# WGA_IR.net
KiCad netlist of a schematic drawn in Altium Designer
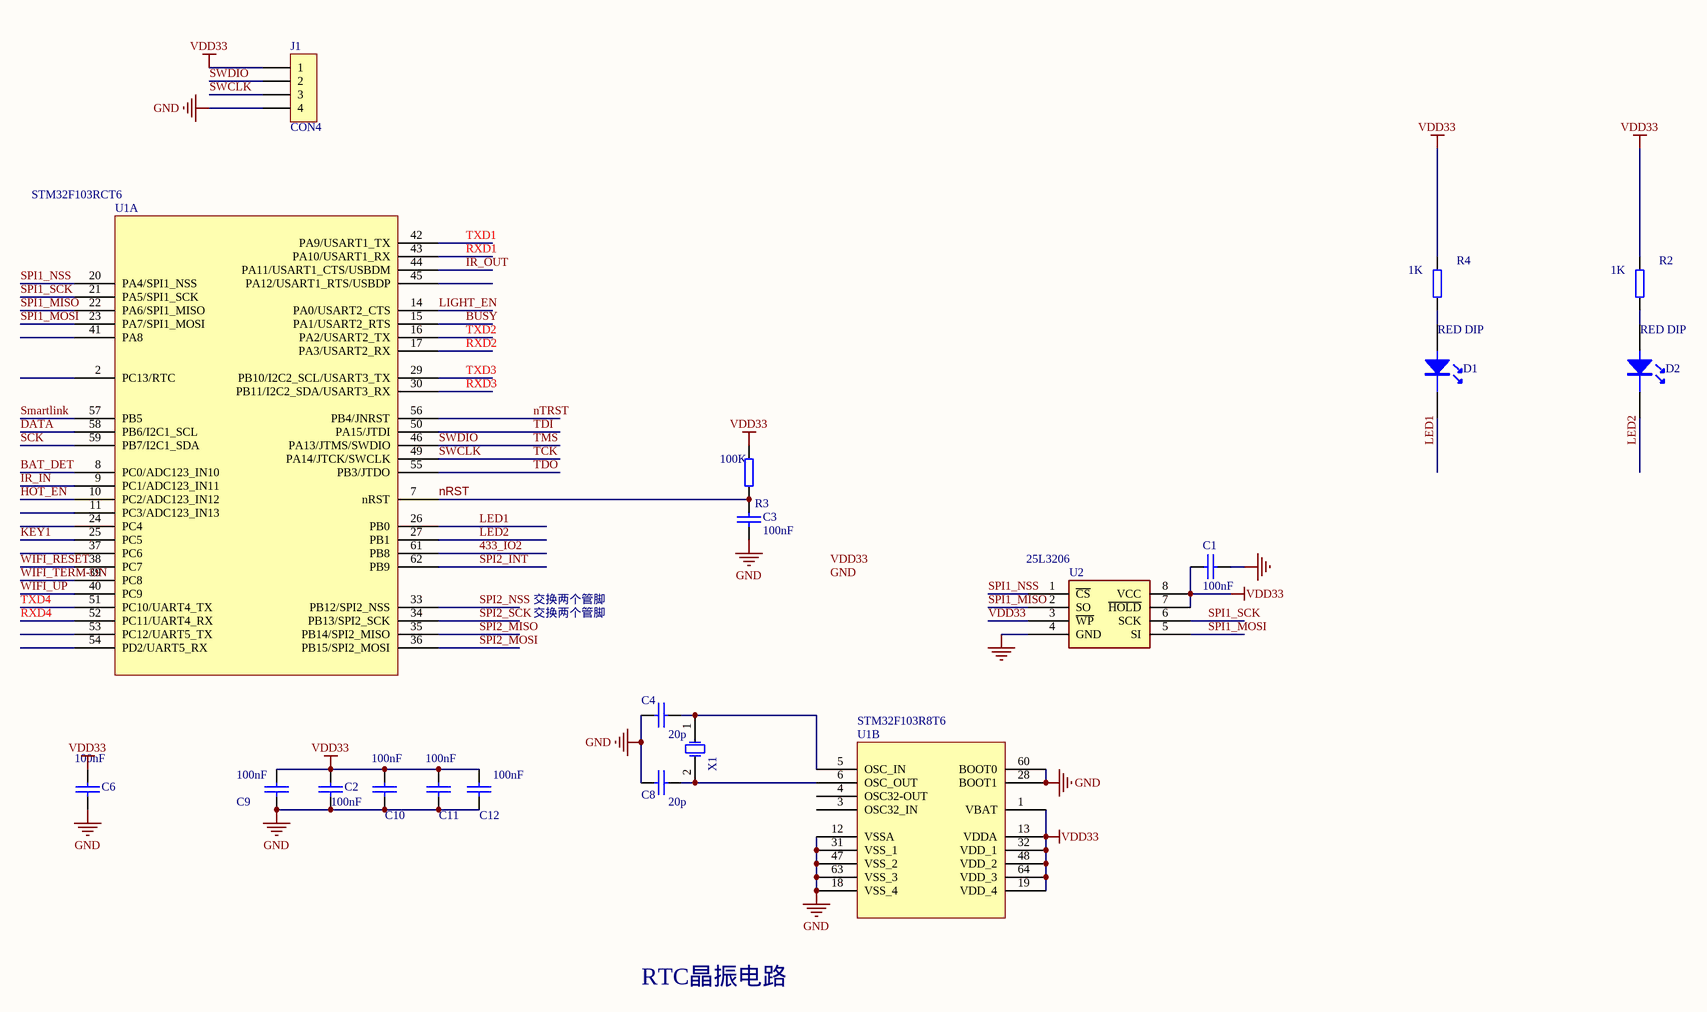
[diagram p0: WGA_IR.SchDoc]

(export (version "E")
  (design (tool "Eeschema 10.0.6"))
  (components
    (comp (ref "C1")
      (value "100nF")
      (footprint "C0603")
      (description "CAP CER 0.1UF 50V Y5V 0603")
      (fields
        (field (name "MANUFACTURER") "Yageo")
        (field (name "MANUFACTURER PART NUMBER") "CC0603ZRY5V9BB104")
      )
      (libsource (lib "") (part "C0603_100nF_1"))
    )
    (comp (ref "C2")
      (value "100nF")
      (footprint "C0603")
      (description "CAP CER 0.1UF 50V Y5V 0603")
      (fields
        (field (name "MANUFACTURER") "Yageo")
        (field (name "MANUFACTURER PART NUMBER") "CC0603ZRY5V9BB104")
      )
      (libsource (lib "") (part "C0603_100nF_1"))
    )
    (comp (ref "C3")
      (value "100nF")
      (footprint "C0603")
      (description "CAP CER 0.1UF 50V Y5V 0603")
      (fields
        (field (name "MANUFACTURER") "Yageo")
        (field (name "MANUFACTURER PART NUMBER") "CC0603ZRY5V9BB104")
      )
      (libsource (lib "电容") (part "C0603_100nF"))
    )
    (comp (ref "C4")
      (value "20p")
      (footprint "C0603")
      (description "CAP CER 20PF 50V 5% NPO 0603")
      (fields
        (field (name "MANUFACTURER") "Yageo")
        (field (name "MANUFACTURER PART NUMBER") "CC0603JRNPO9BN200")
      )
      (libsource (lib "红外微波探测") (part "C0603_20p"))
    )
    (comp (ref "C6")
      (value "100nF")
      (footprint "C0603")
      (description "CAP CER 0.1UF 50V Y5V 0603")
      (fields
        (field (name "MANUFACTURER") "Yageo")
        (field (name "MANUFACTURER PART NUMBER") "CC0603ZRY5V9BB104")
      )
      (libsource (lib "") (part "C0603_100nF_1"))
    )
    (comp (ref "C8")
      (value "20p")
      (footprint "C0603")
      (description "CAP CER 20PF 50V 5% NPO 0603")
      (fields
        (field (name "MANUFACTURER") "Yageo")
        (field (name "MANUFACTURER PART NUMBER") "CC0603JRNPO9BN200")
      )
      (libsource (lib "红外微波探测") (part "C0603_20p"))
    )
    (comp (ref "C9")
      (value "100nF")
      (footprint "C0603")
      (description "CAP CER 0.1UF 50V Y5V 0603")
      (fields
        (field (name "MANUFACTURER") "Yageo")
        (field (name "MANUFACTURER PART NUMBER") "CC0603ZRY5V9BB104")
      )
      (libsource (lib "") (part "C0603_100nF_1"))
    )
    (comp (ref "C10")
      (value "100nF")
      (footprint "C0603")
      (description "CAP CER 0.1UF 50V Y5V 0603")
      (fields
        (field (name "MANUFACTURER") "Yageo")
        (field (name "MANUFACTURER PART NUMBER") "CC0603ZRY5V9BB104")
      )
      (libsource (lib "") (part "C0603_100nF_1"))
    )
    (comp (ref "C11")
      (value "100nF")
      (footprint "C0603")
      (description "CAP CER 0.1UF 50V Y5V 0603")
      (fields
        (field (name "MANUFACTURER") "Yageo")
        (field (name "MANUFACTURER PART NUMBER") "CC0603ZRY5V9BB104")
      )
      (libsource (lib "") (part "C0603_100nF_1"))
    )
    (comp (ref "C12")
      (value "100nF")
      (footprint "C0603")
      (description "CAP CER 0.1UF 50V Y5V 0603")
      (fields
        (field (name "MANUFACTURER") "Yageo")
        (field (name "MANUFACTURER PART NUMBER") "CC0603ZRY5V9BB104")
      )
      (libsource (lib "") (part "C0603_100nF_1"))
    )
    (comp (ref "D1")
      (value "RED DIP")
      (footprint "T1-3MM_N")
      (description "LED SUPER RED 0603 SMD VF=2V  I=20mA")
      (fields
        (field (name "MANUFACTURER") "Vishay Semiconductor Opto Division")
        (field (name "MANUFACTURER PART NUMBER") "VLMS1300-GS08")
      )
      (libsource (lib "二极管") (part "LED-D0603"))
    )
    (comp (ref "D2")
      (value "RED DIP")
      (footprint "T1-3MM_N")
      (description "LED SUPER RED 0603 SMD VF=2V  I=20mA")
      (fields
        (field (name "MANUFACTURER") "Vishay Semiconductor Opto Division")
        (field (name "MANUFACTURER PART NUMBER") "VLMS1300-GS08")
      )
      (libsource (lib "二极管") (part "LED-D0603"))
    )
    (comp (ref "J1")
      (value "CON4")
      (footprint "SIP4")
      (description "2.54mm dip")
      (libsource (lib "接插件") (part "CON4"))
    )
    (comp (ref "R2")
      (value "1K")
      (footprint "R0603")
      (description "RES 1.0K OHM 1/10W 5% 0603 SMD")
      (fields
        (field (name "MANUFACTURER") "Yageo")
        (field (name "MANUFACTURER PART NUMBER") "RC0603JR-071KL")
      )
      (libsource (lib "电阻") (part "R0603_1K_5%"))
    )
    (comp (ref "R3")
      (value "100K")
      (footprint "R0603")
      (description "RES 100K OHM 1/10W 5% 0603 SMD")
      (fields
        (field (name "MANUFACTURER") "Yageo")
        (field (name "MANUFACTURER PART NUMBER") "RC0603JR-07100KL")
      )
      (libsource (lib "电阻") (part "R0603_100K_5%"))
    )
    (comp (ref "R4")
      (value "1K")
      (footprint "R0603")
      (description "RES 1.0K OHM 1/10W 5% 0603 SMD")
      (fields
        (field (name "MANUFACTURER") "Yageo")
        (field (name "MANUFACTURER PART NUMBER") "RC0603JR-071KL")
      )
      (libsource (lib "电阻") (part "R0603_1K_5%"))
    )
    (comp (ref "U1")
      (value "STM32F103RCT6")
      (footprint "LQFP64")
      (description "MCU ARM 128KB FLASH MEM 64-LQFP")
      (fields (field (name "MANUFACTURER") "STMicroelectronics"))
      (libsource (lib "集成电路") (part "STM32F103RC"))
    )
    (comp (ref "U2")
      (value "25L3206")
      (footprint "SSOP8")
      (description "IC FLASH 32MBIT 86MHZ 8SOP 32M (4M x 8)")
      (fields
        (field (name "MANUFACTURER") "Macronix")
        (field (name "MANUFACTURER PART NUMBER") "MX25L3206EM2I-12G")
      )
      (libsource (lib "红外微波探测") (part "25L3206"))
    )
    (comp (ref "X1")
      (value "9C-8.000MBBK-T")
      (footprint "XTAL2")
      (description "CRYSTAL 8.000MHZ 20PF SMD")
      (fields (field (name "MANUFACTURER") "TXC CORPORATION"))
      (libsource (lib "红外微波探测") (part "CRYSTAL-XTAL2"))
    )
  )
  (nets
    (net (code "1") (name "/433_IO2") (class "Default")
      (node (ref "U1") (pin "61") (pinfunction "PB8_61") (pintype "passive"))
    )
    (net (code "2") (name "/BAT_DET") (class "Default")
      (node (ref "U1") (pin "8") (pinfunction "PC0/ADC123_IN10_8") (pintype "passive"))
    )
    (net (code "3") (name "/BUSY") (class "Default")
      (node (ref "U1") (pin "15") (pinfunction "PA1/USART2_RTS_15") (pintype "passive"))
    )
    (net (code "4") (name "/DATA") (class "Default")
      (node (ref "U1") (pin "58") (pinfunction "PB6/I2C1_SCL_58") (pintype "passive"))
    )
    (net (code "5") (name "/HOT_EN") (class "Default")
      (node (ref "U1") (pin "10") (pinfunction "PC2/ADC123_IN12_10") (pintype "passive"))
    )
    (net (code "6") (name "/IR_IN") (class "Default")
      (node (ref "U1") (pin "9") (pinfunction "PC1/ADC123_IN11_9") (pintype "passive"))
    )
    (net (code "7") (name "/IR_OUT") (class "Default")
      (node (ref "U1") (pin "44") (pinfunction "PA11/USART1_CTS/USBDM_44") (pintype "passive"))
    )
    (net (code "8") (name "/KEY1") (class "Default")
      (node (ref "U1") (pin "25") (pinfunction "PC5_25") (pintype "passive"))
    )
    (net (code "9") (name "/LED1") (class "Default")
      (node (ref "D1") (pin "2") (pinfunction "2_2") (pintype "passive"))
      (node (ref "U1") (pin "26") (pinfunction "PB0_26") (pintype "passive"))
    )
    (net (code "10") (name "/LED2") (class "Default")
      (node (ref "D2") (pin "2") (pinfunction "2_2") (pintype "passive"))
      (node (ref "U1") (pin "27") (pinfunction "PB1_27") (pintype "passive"))
    )
    (net (code "11") (name "/LIGHT_EN") (class "Default")
      (node (ref "U1") (pin "14") (pinfunction "PA0/USART2_CTS_14") (pintype "passive"))
    )
    (net (code "12") (name "/RXD1") (class "Default")
      (node (ref "U1") (pin "43") (pinfunction "PA10/USART1_RX_43") (pintype "passive"))
    )
    (net (code "13") (name "/RXD2") (class "Default")
      (node (ref "U1") (pin "17") (pinfunction "PA3/USART2_RX_17") (pintype "passive"))
    )
    (net (code "14") (name "/RXD3") (class "Default")
      (node (ref "U1") (pin "30") (pinfunction "PB11/I2C2_SDA/USART3_RX_30") (pintype "passive"))
    )
    (net (code "15") (name "/RXD4") (class "Default")
      (node (ref "U1") (pin "52") (pinfunction "PC11/UART4_RX_52") (pintype "passive"))
    )
    (net (code "16") (name "/SCK") (class "Default")
      (node (ref "U1") (pin "59") (pinfunction "PB7/I2C1_SDA_59") (pintype "passive"))
    )
    (net (code "17") (name "/SPI1_MISO") (class "Default")
      (node (ref "U1") (pin "22") (pinfunction "PA6/SPI1_MISO_22") (pintype "passive"))
      (node (ref "U2") (pin "2") (pinfunction "SO_2") (pintype "passive"))
    )
    (net (code "18") (name "/SPI1_MOSI") (class "Default")
      (node (ref "U1") (pin "23") (pinfunction "PA7/SPI1_MOSI_23") (pintype "passive"))
      (node (ref "U2") (pin "5") (pinfunction "SI_5") (pintype "passive"))
    )
    (net (code "19") (name "/SPI1_NSS") (class "Default")
      (node (ref "U1") (pin "20") (pinfunction "PA4/SPI1_NSS_20") (pintype "passive"))
      (node (ref "U2") (pin "1") (pinfunction "~{CS}_1") (pintype "passive"))
    )
    (net (code "20") (name "/SPI1_SCK") (class "Default")
      (node (ref "U1") (pin "21") (pinfunction "PA5/SPI1_SCK_21") (pintype "passive"))
      (node (ref "U2") (pin "6") (pinfunction "SCK_6") (pintype "passive"))
    )
    (net (code "21") (name "/SPI2_INT") (class "Default")
      (node (ref "U1") (pin "62") (pinfunction "PB9_62") (pintype "passive"))
    )
    (net (code "22") (name "/SPI2_MISO") (class "Default")
      (node (ref "U1") (pin "35") (pinfunction "PB14/SPI2_MISO_35") (pintype "passive"))
    )
    (net (code "23") (name "/SPI2_MOSI") (class "Default")
      (node (ref "U1") (pin "36") (pinfunction "PB15/SPI2_MOSI_36") (pintype "passive"))
    )
    (net (code "24") (name "/SPI2_NSS") (class "Default")
      (node (ref "U1") (pin "33") (pinfunction "PB12/SPI2_NSS_33") (pintype "passive"))
    )
    (net (code "25") (name "/SPI2_SCK") (class "Default")
      (node (ref "U1") (pin "34") (pinfunction "PB13/SPI2_SCK_34") (pintype "passive"))
    )
    (net (code "26") (name "/SWCLK") (class "Default")
      (node (ref "J1") (pin "3") (pinfunction "3_3") (pintype "passive"))
      (node (ref "U1") (pin "49") (pinfunction "PA14/JTCK/SWCLK_49") (pintype "passive"))
    )
    (net (code "27") (name "/SWDIO") (class "Default")
      (node (ref "J1") (pin "2") (pinfunction "2_2") (pintype "passive"))
      (node (ref "U1") (pin "46") (pinfunction "PA13/JTMS/SWDIO_46") (pintype "passive"))
    )
    (net (code "28") (name "/Smartlink") (class "Default")
      (node (ref "U1") (pin "57") (pinfunction "PB5_57") (pintype "passive"))
    )
    (net (code "29") (name "/TDI") (class "Default")
      (node (ref "U1") (pin "50") (pinfunction "PA15/JTDI_50") (pintype "passive"))
    )
    (net (code "30") (name "/TDO") (class "Default")
      (node (ref "U1") (pin "55") (pinfunction "PB3/JTDO_55") (pintype "passive"))
    )
    (net (code "31") (name "/TXD1") (class "Default")
      (node (ref "U1") (pin "42") (pinfunction "PA9/USART1_TX_42") (pintype "passive"))
    )
    (net (code "32") (name "/TXD2") (class "Default")
      (node (ref "U1") (pin "16") (pinfunction "PA2/USART2_TX_16") (pintype "passive"))
    )
    (net (code "33") (name "/TXD3") (class "Default")
      (node (ref "U1") (pin "29") (pinfunction "PB10/I2C2_SCL/USART3_TX_29") (pintype "passive"))
    )
    (net (code "34") (name "/TXD4") (class "Default")
      (node (ref "U1") (pin "51") (pinfunction "PC10/UART4_TX_51") (pintype "passive"))
    )
    (net (code "35") (name "/WIFI_RESET") (class "Default")
      (node (ref "U1") (pin "38") (pinfunction "PC7_38") (pintype "passive"))
    )
    (net (code "36") (name "/WIFI_TERM-ON") (class "Default")
      (node (ref "U1") (pin "39") (pinfunction "PC8_39") (pintype "passive"))
    )
    (net (code "37") (name "/WIFI_UP") (class "Default")
      (node (ref "U1") (pin "40") (pinfunction "PC9_40") (pintype "passive"))
    )
    (net (code "38") (name "/nRST") (class "Default")
      (node (ref "C3") (pin "2") (pinfunction "2_2") (pintype "passive"))
      (node (ref "R3") (pin "1") (pinfunction "1_1") (pintype "passive"))
      (node (ref "U1") (pin "7") (pinfunction "nRST_7") (pintype "passive"))
    )
    (net (code "39") (name "/nTRST") (class "Default")
      (node (ref "U1") (pin "56") (pinfunction "PB4/JNRST_56") (pintype "passive"))
    )
    (net (code "40") (name "GND") (class "Default")
      (node (ref "C1") (pin "2") (pinfunction "2_2") (pintype "passive"))
      (node (ref "C10") (pin "2") (pinfunction "2_2") (pintype "passive"))
      (node (ref "C11") (pin "2") (pinfunction "2_2") (pintype "passive"))
      (node (ref "C12") (pin "2") (pinfunction "2_2") (pintype "passive"))
      (node (ref "C2") (pin "2") (pinfunction "2_2") (pintype "passive"))
      (node (ref "C3") (pin "1") (pinfunction "1_1") (pintype "passive"))
      (node (ref "C4") (pin "1") (pinfunction "1_1") (pintype "passive"))
      (node (ref "C6") (pin "2") (pinfunction "2_2") (pintype "passive"))
      (node (ref "C8") (pin "1") (pinfunction "1_1") (pintype "passive"))
      (node (ref "C9") (pin "2") (pinfunction "2_2") (pintype "passive"))
      (node (ref "J1") (pin "4") (pinfunction "4_4") (pintype "passive"))
      (node (ref "U1") (pin "12") (pinfunction "VSSA_12") (pintype "passive"))
      (node (ref "U1") (pin "18") (pinfunction "VSS_4_18") (pintype "passive"))
      (node (ref "U1") (pin "28") (pinfunction "BOOT1_28") (pintype "passive"))
      (node (ref "U1") (pin "31") (pinfunction "VSS_1_31") (pintype "passive"))
      (node (ref "U1") (pin "47") (pinfunction "VSS_2_47") (pintype "passive"))
      (node (ref "U1") (pin "60") (pinfunction "BOOT0_60") (pintype "passive"))
      (node (ref "U1") (pin "63") (pinfunction "VSS_3_63") (pintype "passive"))
      (node (ref "U2") (pin "4") (pinfunction "GND_4") (pintype "passive"))
    )
    (net (code "41") (name "Net-(D1-Pad1)") (class "Default")
      (node (ref "D1") (pin "1") (pinfunction "1_1") (pintype "passive"))
      (node (ref "R4") (pin "1") (pinfunction "1_1") (pintype "passive"))
    )
    (net (code "42") (name "Net-(D2-Pad1)") (class "Default")
      (node (ref "D2") (pin "1") (pinfunction "1_1") (pintype "passive"))
      (node (ref "R2") (pin "1") (pinfunction "1_1") (pintype "passive"))
    )
    (net (code "43") (name "Net-(U1B-OSC_IN)") (class "Default")
      (node (ref "C4") (pin "2") (pinfunction "2_2") (pintype "passive"))
      (node (ref "U1") (pin "5") (pinfunction "OSC_IN_5") (pintype "passive"))
      (node (ref "X1") (pin "1") (pinfunction "OSC1_1") (pintype "passive"))
    )
    (net (code "44") (name "Net-(U1B-OSC_OUT)") (class "Default")
      (node (ref "C8") (pin "2") (pinfunction "2_2") (pintype "passive"))
      (node (ref "U1") (pin "6") (pinfunction "OSC_OUT_6") (pintype "passive"))
      (node (ref "X1") (pin "2") (pinfunction "OSC2_2") (pintype "passive"))
    )
    (net (code "45") (name "VDD33") (class "Default")
      (node (ref "C1") (pin "1") (pinfunction "1_1") (pintype "passive"))
      (node (ref "C10") (pin "1") (pinfunction "1_1") (pintype "passive"))
      (node (ref "C11") (pin "1") (pinfunction "1_1") (pintype "passive"))
      (node (ref "C12") (pin "1") (pinfunction "1_1") (pintype "passive"))
      (node (ref "C2") (pin "1") (pinfunction "1_1") (pintype "passive"))
      (node (ref "C6") (pin "1") (pinfunction "1_1") (pintype "passive"))
      (node (ref "C9") (pin "1") (pinfunction "1_1") (pintype "passive"))
      (node (ref "J1") (pin "1") (pinfunction "1_1") (pintype "passive"))
      (node (ref "R2") (pin "2") (pinfunction "2_2") (pintype "passive"))
      (node (ref "R3") (pin "2") (pinfunction "2_2") (pintype "passive"))
      (node (ref "R4") (pin "2") (pinfunction "2_2") (pintype "passive"))
      (node (ref "U1") (pin "1") (pinfunction "VBAT_1") (pintype "passive"))
      (node (ref "U1") (pin "13") (pinfunction "VDDA_13") (pintype "passive"))
      (node (ref "U1") (pin "19") (pinfunction "VDD_4_19") (pintype "passive"))
      (node (ref "U1") (pin "32") (pinfunction "VDD_1_32") (pintype "passive"))
      (node (ref "U1") (pin "48") (pinfunction "VDD_2_48") (pintype "passive"))
      (node (ref "U1") (pin "64") (pinfunction "VDD_3_64") (pintype "passive"))
      (node (ref "U2") (pin "3") (pinfunction "~{WP}_3") (pintype "passive"))
      (node (ref "U2") (pin "7") (pinfunction "~{HOLD}_7") (pintype "passive"))
      (node (ref "U2") (pin "8") (pinfunction "VCC_8") (pintype "passive"))
    )
    (net (code "46") (name "unconnected-(U1A-PA8-Pad41)") (class "Default")
      (node (ref "U1") (pin "41") (pinfunction "PA8_41") (pintype "passive"))
    )
    (net (code "47") (name "unconnected-(U1A-PA12{slash}USART1_RTS{slash}USBDP-Pad45)") (class "Default")
      (node (ref "U1") (pin "45") (pinfunction "PA12/USART1_RTS/USBDP_45") (pintype "passive"))
    )
    (net (code "48") (name "unconnected-(U1A-PC3{slash}ADC123_IN13-Pad11)") (class "Default")
      (node (ref "U1") (pin "11") (pinfunction "PC3/ADC123_IN13_11") (pintype "passive"))
    )
    (net (code "49") (name "unconnected-(U1A-PC4-Pad24)") (class "Default")
      (node (ref "U1") (pin "24") (pinfunction "PC4_24") (pintype "passive"))
    )
    (net (code "50") (name "unconnected-(U1A-PC6-Pad37)") (class "Default")
      (node (ref "U1") (pin "37") (pinfunction "PC6_37") (pintype "passive"))
    )
    (net (code "51") (name "unconnected-(U1A-PC12{slash}UART5_TX-Pad53)") (class "Default")
      (node (ref "U1") (pin "53") (pinfunction "PC12/UART5_TX_53") (pintype "passive"))
    )
    (net (code "52") (name "unconnected-(U1A-PC13{slash}RTC-Pad2)") (class "Default")
      (node (ref "U1") (pin "2") (pinfunction "PC13/RTC_2") (pintype "passive"))
    )
    (net (code "53") (name "unconnected-(U1A-PD2{slash}UART5_RX-Pad54)") (class "Default")
      (node (ref "U1") (pin "54") (pinfunction "PD2/UART5_RX_54") (pintype "passive"))
    )
    (net (code "54") (name "unconnected-(U1B-OSC32-OUT-Pad4)") (class "Default")
      (node (ref "U1") (pin "4") (pinfunction "OSC32-OUT_4") (pintype "passive"))
    )
    (net (code "55") (name "unconnected-(U1B-OSC32_IN-Pad3)") (class "Default")
      (node (ref "U1") (pin "3") (pinfunction "OSC32_IN_3") (pintype "passive"))
    )
  )
)
